# US_SB_OS.net
KiCad netlist of a schematic drawn in Altium Designer
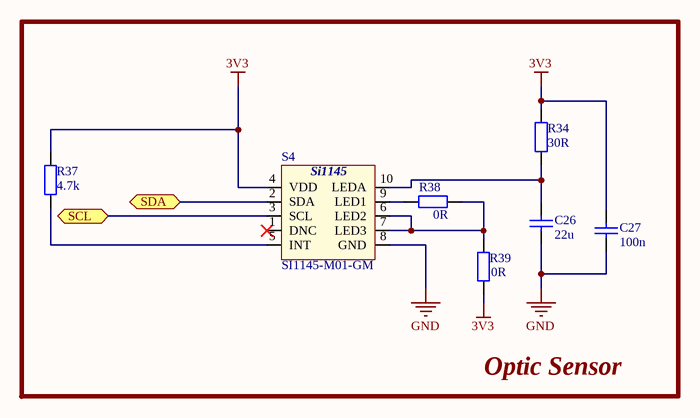
[diagram p0: US_SB_OS.SchDoc]

(export (version "E")
  (design (tool "Eeschema 10.0.6"))
  (components
    (comp (ref "C26")
      (value "22u")
      (footprint "C0805_IPC_HD")
      (description "CAP CER 22UF 16V X5R 0805")
      (fields
        (field (name "MANUFACTURER") "Samsung Electro-Mechanics")
        (field (name "MANUFACTURER PART NUMBER") "CL21A226MOCLRNC")
      )
      (libsource (lib "alfasat_lib") (part "CL21A226MOCLRNC"))
    )
    (comp (ref "C27")
      (value "100n")
      (footprint "C0603_IPC_HD")
      (description "CAP CER 0.1UF 16V X7R 0603")
      (fields
        (field (name "MANUFACTURER") "Samsung Electro-Mechanics")
        (field (name "MANUFACTURER PART NUMBER") "CL10B104KO8NNNC")
      )
      (libsource (lib "alfasat_parts_lib") (part "CL10B104KO8NNNC"))
    )
    (comp (ref "R34")
      (value "30R")
      (footprint "C0603_IPC_HD")
      (description "RES SMD 30 OHM 5% 1/10W 0603")
      (fields
        (field (name "MANUFACTURER") "Bourns Inc.")
        (field (name "MANUFACTURER PART NUMBER") "CR0603-JW-300ELF")
      )
      (libsource (lib "alfasat_lib_eps") (part "CR0603-JW-30Ohm"))
    )
    (comp (ref "R37")
      (value "4.7k")
      (footprint "R0603_IPC_HD")
      (description "RES SMD 4.7K OHM 5% 1/10W 0603")
      (fields
        (field (name "MANUFACTURER") "Bourns Inc.")
        (field (name "MANUFACTURER PART NUMBER") "CR0603-JW-472ELF")
      )
      (libsource (lib "alfasat_lib_eps") (part "CR0603-JW-4.7k"))
    )
    (comp (ref "R38")
      (value "0R")
      (footprint "R0603_IPC_MD")
      (description "RES SMD 0 OHM JUMPER 1/10W 0603")
      (fields
        (field (name "MANUFACTURER") "Bourns Inc.")
        (field (name "MANUFACTURER PART NUMBER") "CR0603-J/-000ELF")
      )
      (libsource (lib "alfasat_lib") (part "CR0603-J/-000ELF"))
    )
    (comp (ref "R39")
      (value "0R")
      (footprint "R0603_IPC_MD")
      (description "RES SMD 0 OHM JUMPER 1/10W 0603")
      (fields
        (field (name "MANUFACTURER") "Bourns Inc.")
        (field (name "MANUFACTURER PART NUMBER") "CR0603-J/-000ELF")
      )
      (libsource (lib "") (part "CR0603-J/-000ELF_1"))
    )
    (comp (ref "S4")
      (value "SI1145-M01-GM")
      (footprint "Si1145")
      (description "Optical Sensor Ambient, IR, Ultraviolet (UV) 850nm I²C 10-SMD Module, No Lead")
      (fields (field (name "MANUFACTURER") "Silicon Labs"))
      (libsource (lib "alfasat_lib_eps") (part "Si1145"))
    )
  )
  (nets
    (net (code "1") (name "/SCL") (class "Default")
      (node (ref "S4") (pin "3") (pinfunction "SCL_3") (pintype "passive"))
    )
    (net (code "2") (name "/SDA") (class "Default")
      (node (ref "S4") (pin "2") (pinfunction "SDA_2") (pintype "passive"))
    )
    (net (code "3") (name "3V3") (class "Default")
      (node (ref "C27") (pin "1") (pinfunction "1_1") (pintype "passive"))
      (node (ref "R34") (pin "1") (pinfunction "1_1") (pintype "passive"))
      (node (ref "R37") (pin "2") (pinfunction "2_2") (pintype "passive"))
      (node (ref "R39") (pin "2") (pinfunction "2_2") (pintype "passive"))
      (node (ref "S4") (pin "4") (pinfunction "VDD_4") (pintype "passive"))
    )
    (net (code "4") (name "GND") (class "Default")
      (node (ref "C26") (pin "1") (pinfunction "1_1") (pintype "passive"))
      (node (ref "C27") (pin "2") (pinfunction "2_2") (pintype "passive"))
      (node (ref "S4") (pin "8") (pinfunction "GND_8") (pintype "passive"))
    )
    (net (code "5") (name "Net-(S4-INT)") (class "Default")
      (node (ref "R37") (pin "1") (pinfunction "1_1") (pintype "passive"))
      (node (ref "S4") (pin "5") (pinfunction "INT_5") (pintype "passive"))
    )
    (net (code "6") (name "Net-(S4-LED1)") (class "Default")
      (node (ref "R38") (pin "2") (pinfunction "2_2") (pintype "passive"))
      (node (ref "S4") (pin "9") (pinfunction "LED1_9") (pintype "passive"))
    )
    (net (code "7") (name "Net-(S4-LED2)") (class "Default")
      (node (ref "R38") (pin "1") (pinfunction "1_1") (pintype "passive"))
      (node (ref "R39") (pin "1") (pinfunction "1_1") (pintype "passive"))
      (node (ref "S4") (pin "6") (pinfunction "LED2_6") (pintype "passive"))
      (node (ref "S4") (pin "7") (pinfunction "LED3_7") (pintype "passive"))
    )
    (net (code "8") (name "Net-(S4-LEDA)") (class "Default")
      (node (ref "C26") (pin "2") (pinfunction "2_2") (pintype "passive"))
      (node (ref "R34") (pin "2") (pinfunction "2_2") (pintype "passive"))
      (node (ref "S4") (pin "10") (pinfunction "LEDA_10") (pintype "passive"))
    )
    (net (code "9") (name "unconnected-(S4-DNC-Pad1)") (class "Default")
      (node (ref "S4") (pin "1") (pinfunction "DNC_1") (pintype "passive+no_connect"))
    )
  )
)
